# mag-baro.net
KiCad netlist of a schematic drawn in EAGLE
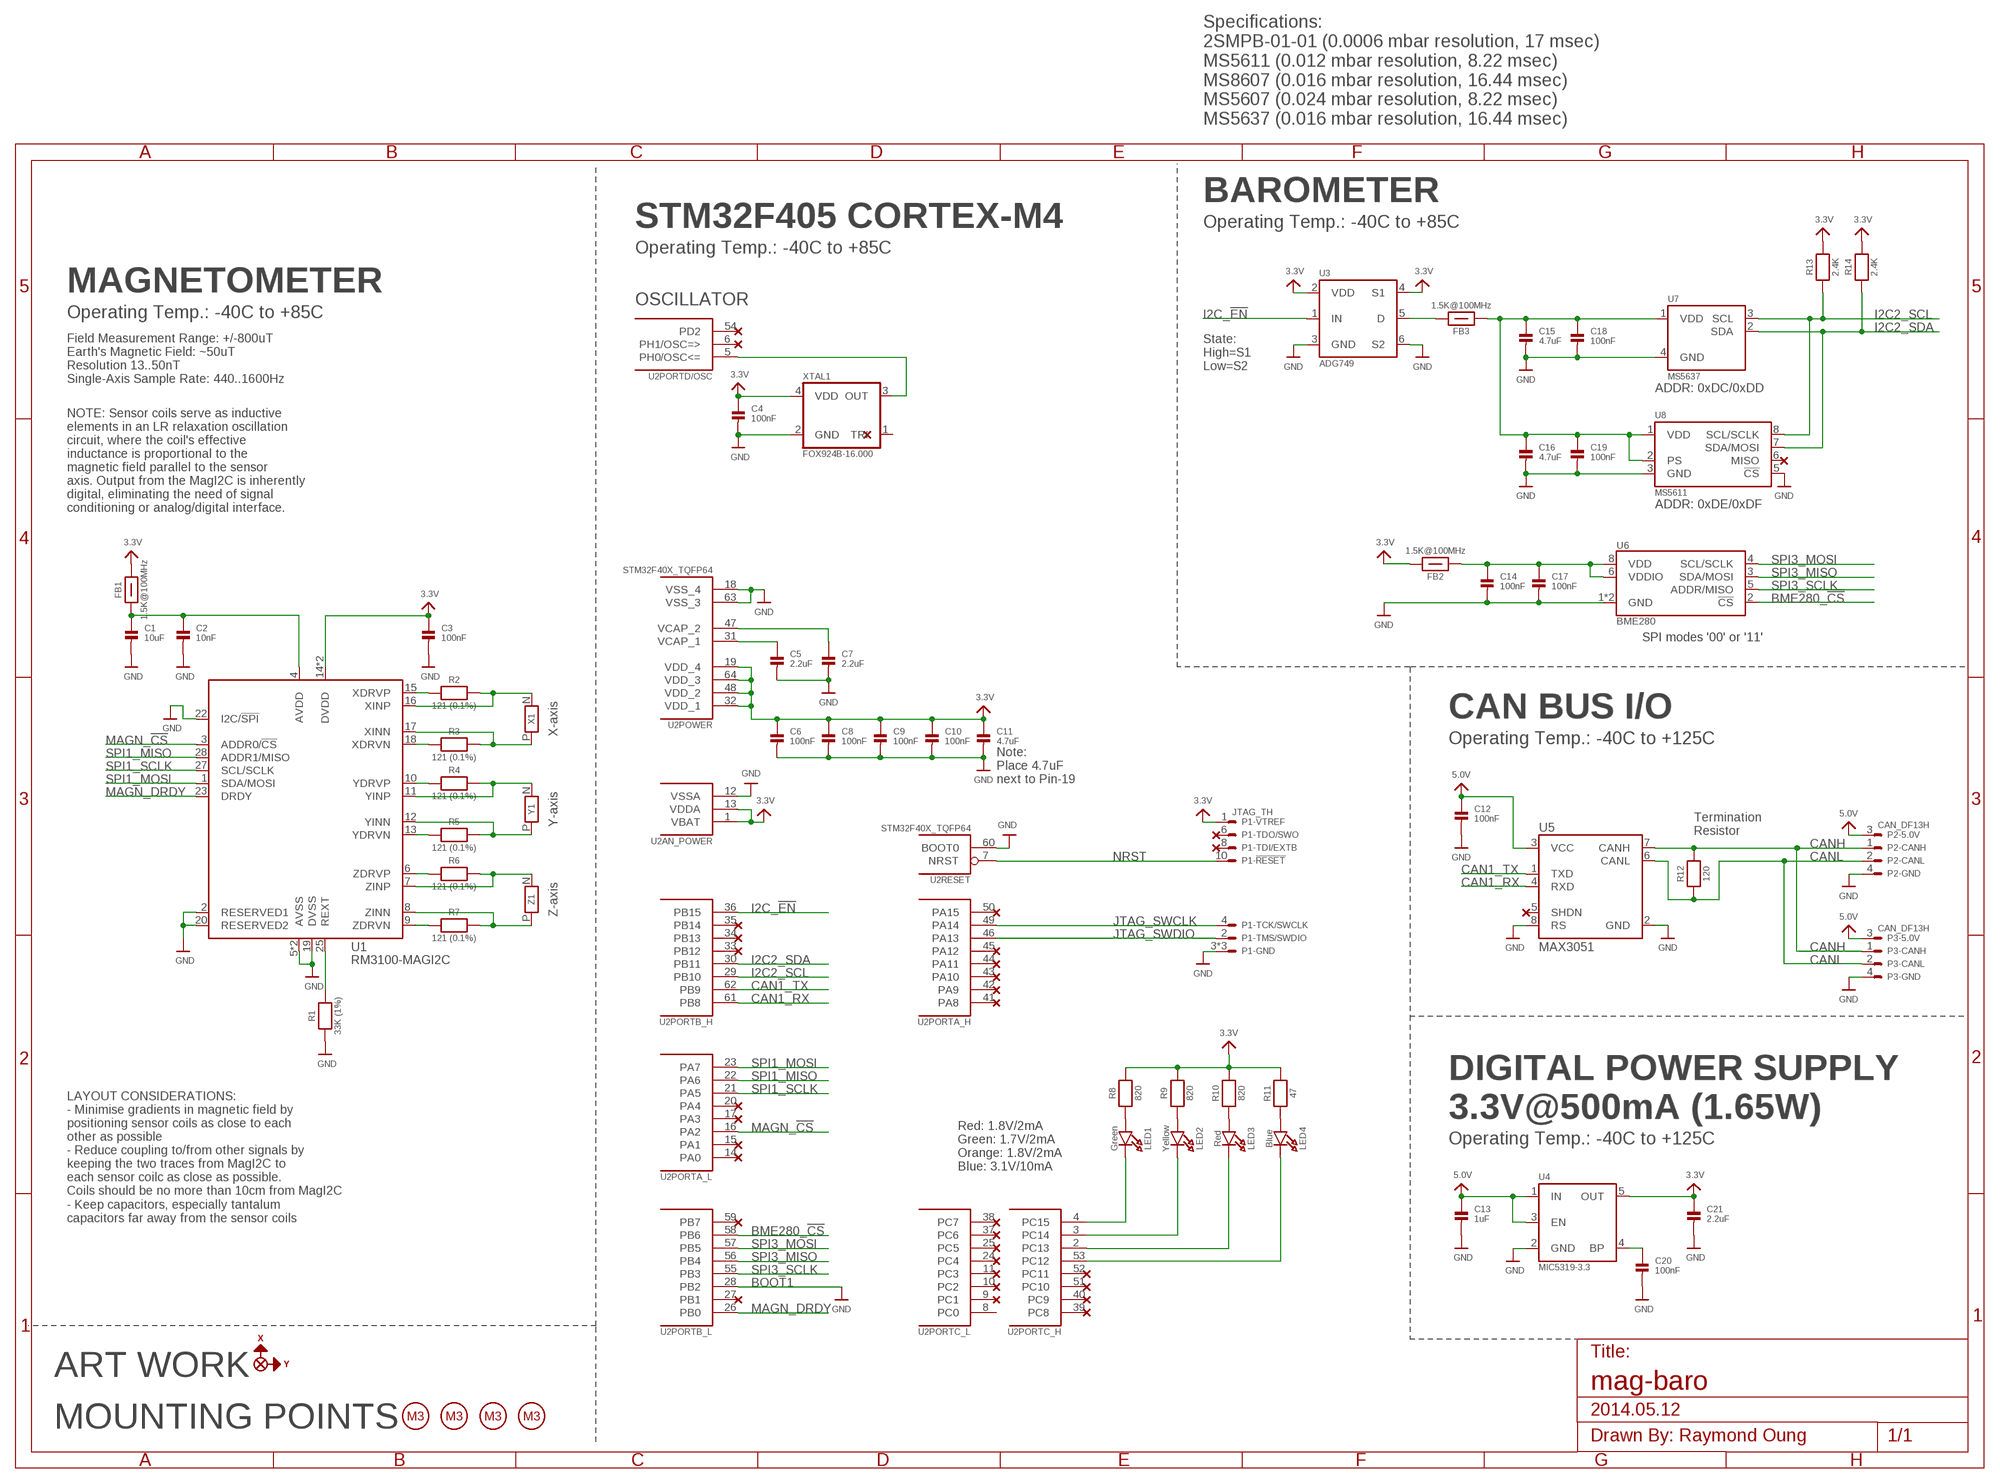
[diagram p0: schematic, sheet 1]

(export (version "E")
  (design (tool "Eeschema 10.0.6"))
  (components
    (comp (ref "AXIS3D2")
      (value "AXIS3D_DOWN")
      (footprint "eagle-import:AXIS3D_DOWN")
      (libsource (lib "eagle-import") (part "AXIS3D_DOWN"))
    )
    (comp (ref "C1")
      (value "10uF")
      (footprint "eagle-import:0402")
      (libsource (lib "eagle-import") (part "CAP_CERAMIC0402"))
    )
    (comp (ref "C2")
      (value "10nF")
      (footprint "eagle-import:0402")
      (libsource (lib "eagle-import") (part "CAP_CERAMIC0402"))
    )
    (comp (ref "C3")
      (value "100nF")
      (footprint "eagle-import:0402")
      (libsource (lib "eagle-import") (part "CAP_CERAMIC0402"))
    )
    (comp (ref "C4")
      (value "100nF")
      (footprint "eagle-import:0402")
      (libsource (lib "eagle-import") (part "CAP_CERAMIC0402"))
    )
    (comp (ref "C5")
      (value "2.2uF")
      (footprint "eagle-import:0402")
      (libsource (lib "eagle-import") (part "CAP_CERAMIC0402"))
    )
    (comp (ref "C6")
      (value "100nF")
      (footprint "eagle-import:0402")
      (libsource (lib "eagle-import") (part "CAP_CERAMIC0402"))
    )
    (comp (ref "C7")
      (value "2.2uF")
      (footprint "eagle-import:0402")
      (libsource (lib "eagle-import") (part "CAP_CERAMIC0402"))
    )
    (comp (ref "C8")
      (value "100nF")
      (footprint "eagle-import:0402")
      (libsource (lib "eagle-import") (part "CAP_CERAMIC0402"))
    )
    (comp (ref "C9")
      (value "100nF")
      (footprint "eagle-import:0402")
      (libsource (lib "eagle-import") (part "CAP_CERAMIC0402"))
    )
    (comp (ref "C10")
      (value "100nF")
      (footprint "eagle-import:0402")
      (libsource (lib "eagle-import") (part "CAP_CERAMIC0402"))
    )
    (comp (ref "C11")
      (value "4.7uF")
      (footprint "eagle-import:0402")
      (libsource (lib "eagle-import") (part "CAP_CERAMIC0402"))
    )
    (comp (ref "C12")
      (value "100nF")
      (footprint "eagle-import:0402")
      (libsource (lib "eagle-import") (part "CAP_CERAMIC0402"))
    )
    (comp (ref "C13")
      (value "1uF")
      (footprint "eagle-import:0402")
      (libsource (lib "eagle-import") (part "CAP_CERAMIC0402"))
    )
    (comp (ref "C14")
      (value "100nF")
      (footprint "eagle-import:0402")
      (libsource (lib "eagle-import") (part "CAP_CERAMIC0402"))
    )
    (comp (ref "C15")
      (value "4.7uF")
      (footprint "eagle-import:0402")
      (libsource (lib "eagle-import") (part "CAP_CERAMIC0402"))
    )
    (comp (ref "C16")
      (value "4.7uF")
      (footprint "eagle-import:0402")
      (libsource (lib "eagle-import") (part "CAP_CERAMIC0402"))
    )
    (comp (ref "C17")
      (value "100nF")
      (footprint "eagle-import:0402")
      (libsource (lib "eagle-import") (part "CAP_CERAMIC0402"))
    )
    (comp (ref "C18")
      (value "100nF")
      (footprint "eagle-import:0402")
      (libsource (lib "eagle-import") (part "CAP_CERAMIC0402"))
    )
    (comp (ref "C19")
      (value "100nF")
      (footprint "eagle-import:0402")
      (libsource (lib "eagle-import") (part "CAP_CERAMIC0402"))
    )
    (comp (ref "C20")
      (value "100nF")
      (footprint "eagle-import:0402")
      (libsource (lib "eagle-import") (part "CAP_CERAMIC0402"))
    )
    (comp (ref "C21")
      (value "2.2uF")
      (footprint "eagle-import:0402")
      (libsource (lib "eagle-import") (part "CAP_CERAMIC0402"))
    )
    (comp (ref "FB1")
      (value "1.5K@100MHz")
      (footprint "eagle-import:0402")
      (libsource (lib "eagle-import") (part "FERRITE_0402"))
    )
    (comp (ref "FB2")
      (value "1.5K@100MHz")
      (footprint "eagle-import:0402")
      (libsource (lib "eagle-import") (part "FERRITE_0402"))
    )
    (comp (ref "FB3")
      (value "1.5K@100MHz")
      (footprint "eagle-import:0402")
      (libsource (lib "eagle-import") (part "FERRITE_0402"))
    )
    (comp (ref "LED1")
      (value "Green")
      (footprint "eagle-import:CHIPLED_0603")
      (libsource (lib "eagle-import") (part "LED_0603"))
    )
    (comp (ref "LED2")
      (value "Yellow")
      (footprint "eagle-import:CHIPLED_0603")
      (libsource (lib "eagle-import") (part "LED_0603"))
    )
    (comp (ref "LED3")
      (value "Red")
      (footprint "eagle-import:CHIPLED_0603")
      (libsource (lib "eagle-import") (part "LED_0603"))
    )
    (comp (ref "LED4")
      (value "Blue")
      (footprint "eagle-import:CHIPLED_0603")
      (libsource (lib "eagle-import") (part "LED_0603"))
    )
    (comp (ref "MP1")
      (value "M3_5")
      (footprint "eagle-import:MP_M3-5")
      (libsource (lib "eagle-import") (part "M3_5"))
    )
    (comp (ref "MP2")
      (value "M3_5")
      (footprint "eagle-import:MP_M3-5")
      (libsource (lib "eagle-import") (part "M3_5"))
    )
    (comp (ref "MP3")
      (value "M3_5")
      (footprint "eagle-import:MP_M3-5")
      (libsource (lib "eagle-import") (part "M3_5"))
    )
    (comp (ref "MP4")
      (value "M3_5")
      (footprint "eagle-import:MP_M3-5")
      (libsource (lib "eagle-import") (part "M3_5"))
    )
    (comp (ref "P1")
      (value "JTAG_TH")
      (footprint "eagle-import:FTSH-105-01-XXX-DV")
      (libsource (lib "eagle-import") (part "JTAG_TH"))
    )
    (comp (ref "P2")
      (value "CAN_DF13H")
      (footprint "eagle-import:DF13A-4P-1.25H")
      (libsource (lib "eagle-import") (part "CAN_DF13H"))
    )
    (comp (ref "P3")
      (value "CAN_DF13H")
      (footprint "eagle-import:DF13A-4P-1.25H")
      (libsource (lib "eagle-import") (part "CAN_DF13H"))
    )
    (comp (ref "R1")
      (value "33K (1%)")
      (footprint "eagle-import:0402")
      (libsource (lib "eagle-import") (part "RESISTOR0402"))
    )
    (comp (ref "R2")
      (value "121 (0.1%)")
      (footprint "eagle-import:0402")
      (libsource (lib "eagle-import") (part "RESISTOR0402"))
    )
    (comp (ref "R3")
      (value "121 (0.1%)")
      (footprint "eagle-import:0402")
      (libsource (lib "eagle-import") (part "RESISTOR0402"))
    )
    (comp (ref "R4")
      (value "121 (0.1%)")
      (footprint "eagle-import:0402")
      (libsource (lib "eagle-import") (part "RESISTOR0402"))
    )
    (comp (ref "R5")
      (value "121 (0.1%)")
      (footprint "eagle-import:0402")
      (libsource (lib "eagle-import") (part "RESISTOR0402"))
    )
    (comp (ref "R6")
      (value "121 (0.1%)")
      (footprint "eagle-import:0402")
      (libsource (lib "eagle-import") (part "RESISTOR0402"))
    )
    (comp (ref "R7")
      (value "121 (0.1%)")
      (footprint "eagle-import:0402")
      (libsource (lib "eagle-import") (part "RESISTOR0402"))
    )
    (comp (ref "R8")
      (value "820")
      (footprint "eagle-import:0402")
      (libsource (lib "eagle-import") (part "RESISTOR0402"))
    )
    (comp (ref "R9")
      (value "820")
      (footprint "eagle-import:0402")
      (libsource (lib "eagle-import") (part "RESISTOR0402"))
    )
    (comp (ref "R10")
      (value "820")
      (footprint "eagle-import:0402")
      (libsource (lib "eagle-import") (part "RESISTOR0402"))
    )
    (comp (ref "R11")
      (value "47")
      (footprint "eagle-import:0402")
      (libsource (lib "eagle-import") (part "RESISTOR0402"))
    )
    (comp (ref "R12")
      (value "120")
      (footprint "eagle-import:0603")
      (libsource (lib "eagle-import") (part "RESISTOR0603"))
    )
    (comp (ref "R13")
      (value "2.4K")
      (footprint "eagle-import:0402")
      (libsource (lib "eagle-import") (part "RESISTOR0402"))
    )
    (comp (ref "R14")
      (value "2.4K")
      (footprint "eagle-import:0402")
      (libsource (lib "eagle-import") (part "RESISTOR0402"))
    )
    (comp (ref "U1")
      (value "RM3100-MAGI2C")
      (footprint "eagle-import:RM3100-MAGI2C")
      (libsource (lib "eagle-import") (part "RM3100-MAGI2C"))
    )
    (comp (ref "U2")
      (value "STM32F40X_TQFP64")
      (footprint "eagle-import:TQFP64")
      (libsource (lib "eagle-import") (part "STM32F40X_TQFP64"))
    )
    (comp (ref "U3")
      (value "ADG749")
      (footprint "eagle-import:SOT363")
      (libsource (lib "eagle-import") (part "ADG749"))
    )
    (comp (ref "U4")
      (value "MIC5319-3.3")
      (footprint "eagle-import:SOT23-5")
      (libsource (lib "eagle-import") (part "MIC5319-3.3"))
    )
    (comp (ref "U5")
      (value "MAX3051")
      (footprint "eagle-import:SOT23-8")
      (libsource (lib "eagle-import") (part "MAX3051"))
    )
    (comp (ref "U6")
      (value "BME280")
      (footprint "eagle-import:BME280_LGA_MANUAL")
      (libsource (lib "eagle-import") (part "BME280_MANUAL"))
    )
    (comp (ref "U7")
      (value "MS5637")
      (footprint "eagle-import:MS5637")
      (libsource (lib "eagle-import") (part "MS5637"))
    )
    (comp (ref "U8")
      (value "MS5611")
      (footprint "eagle-import:MS5611")
      (libsource (lib "eagle-import") (part "MS5611"))
    )
    (comp (ref "X1")
      (value "RM3XXX-SEN-X")
      (footprint "eagle-import:RM3XXX-SEN-XY")
      (libsource (lib "eagle-import") (part "RM3XXX-SEN-X"))
    )
    (comp (ref "XTAL1")
      (value "FOX924B-16.000")
      (footprint "eagle-import:OSCILLATOR-5.0X3.2A")
      (libsource (lib "eagle-import") (part "TCXO_5.0X3.2A"))
    )
    (comp (ref "Y1")
      (value "RM3XXX-SEN-Y")
      (footprint "eagle-import:RM3XXX-SEN-XY")
      (libsource (lib "eagle-import") (part "RM3XXX-SEN-Y"))
    )
    (comp (ref "Z1")
      (value "RM3XXX-SEN-Z")
      (footprint "eagle-import:RM3XXX-SEN_Z")
      (libsource (lib "eagle-import") (part "RM3XXX-SEN-Z"))
    )
  )
  (nets
    (net (code "1") (name "/BME280_~{CS}") (class "Default")
      (node (ref "U2") (pin "58") (pinfunction "PB6_58") (pintype "bidirectional"))
      (node (ref "U6") (pin "2") (pinfunction "~{CS}_2") (pintype "bidirectional"))
    )
    (net (code "2") (name "/CAN1_RX") (class "Default")
      (node (ref "U2") (pin "61") (pinfunction "PB8_61") (pintype "bidirectional"))
      (node (ref "U5") (pin "4") (pinfunction "RXD_4") (pintype "bidirectional"))
    )
    (net (code "3") (name "/CAN1_TX") (class "Default")
      (node (ref "U2") (pin "62") (pinfunction "PB9_62") (pintype "bidirectional"))
      (node (ref "U5") (pin "1") (pinfunction "TXD_1") (pintype "bidirectional"))
    )
    (net (code "4") (name "/CANH") (class "Default")
      (node (ref "P2") (pin "1") (pinfunction "S_1") (pintype "passive"))
      (node (ref "P3") (pin "1") (pinfunction "S_1") (pintype "passive"))
      (node (ref "R12") (pin "2") (pinfunction "2_2") (pintype "passive"))
      (node (ref "U5") (pin "7") (pinfunction "CANH_7") (pintype "bidirectional"))
    )
    (net (code "5") (name "/CANL") (class "Default")
      (node (ref "P2") (pin "2") (pinfunction "S_2") (pintype "passive"))
      (node (ref "P3") (pin "2") (pinfunction "S_2") (pintype "passive"))
      (node (ref "R12") (pin "1") (pinfunction "1_1") (pintype "passive"))
      (node (ref "U5") (pin "6") (pinfunction "CANL_6") (pintype "bidirectional"))
    )
    (net (code "6") (name "/I2C2_SCL") (class "Default")
      (node (ref "R13") (pin "1") (pinfunction "1_1") (pintype "passive"))
      (node (ref "U2") (pin "29") (pinfunction "PB10_29") (pintype "bidirectional"))
      (node (ref "U7") (pin "3") (pinfunction "SCL_3") (pintype "bidirectional"))
      (node (ref "U8") (pin "8") (pinfunction "SCL/SCLK_8") (pintype "bidirectional"))
    )
    (net (code "7") (name "/I2C2_SDA") (class "Default")
      (node (ref "R14") (pin "1") (pinfunction "1_1") (pintype "passive"))
      (node (ref "U2") (pin "30") (pinfunction "PB11_30") (pintype "bidirectional"))
      (node (ref "U7") (pin "2") (pinfunction "SDA_2") (pintype "bidirectional"))
      (node (ref "U8") (pin "7") (pinfunction "SDA/MOSI_7") (pintype "bidirectional"))
    )
    (net (code "8") (name "/I2C_~{EN}") (class "Default")
      (node (ref "U2") (pin "36") (pinfunction "PB15_36") (pintype "bidirectional"))
      (node (ref "U3") (pin "1") (pinfunction "IN_1") (pintype "bidirectional"))
    )
    (net (code "9") (name "/JTAG_SWCLK") (class "Default")
      (node (ref "P1") (pin "4") (pinfunction "S_4") (pintype "passive"))
      (node (ref "U2") (pin "49") (pinfunction "PA14_49") (pintype "bidirectional"))
    )
    (net (code "10") (name "/JTAG_SWDIO") (class "Default")
      (node (ref "P1") (pin "2") (pinfunction "S_2") (pintype "passive"))
      (node (ref "U2") (pin "46") (pinfunction "PA13_46") (pintype "bidirectional"))
    )
    (net (code "11") (name "/MAGN_DRDY") (class "Default")
      (node (ref "U1") (pin "23") (pinfunction "DRDY_23") (pintype "bidirectional"))
      (node (ref "U2") (pin "26") (pinfunction "PB0_26") (pintype "bidirectional"))
    )
    (net (code "12") (name "/MAGN_~{CS}") (class "Default")
      (node (ref "U1") (pin "3") (pinfunction "ADDR0/~{CS}_3") (pintype "bidirectional"))
      (node (ref "U2") (pin "16") (pinfunction "PA2_16") (pintype "bidirectional"))
    )
    (net (code "13") (name "/NRST") (class "Default")
      (node (ref "P1") (pin "10") (pinfunction "S_10") (pintype "passive"))
      (node (ref "U2") (pin "7") (pinfunction "NRST_7") (pintype "input"))
    )
    (net (code "14") (name "/SPI1_MISO") (class "Default")
      (node (ref "U1") (pin "28") (pinfunction "ADDR1/MISO_28") (pintype "bidirectional"))
      (node (ref "U2") (pin "22") (pinfunction "PA6_22") (pintype "bidirectional"))
    )
    (net (code "15") (name "/SPI1_MOSI") (class "Default")
      (node (ref "U1") (pin "1") (pinfunction "SDA/MOSI_1") (pintype "bidirectional"))
      (node (ref "U2") (pin "23") (pinfunction "PA7_23") (pintype "bidirectional"))
    )
    (net (code "16") (name "/SPI1_SCLK") (class "Default")
      (node (ref "U1") (pin "27") (pinfunction "SCL/SCLK_27") (pintype "bidirectional"))
      (node (ref "U2") (pin "21") (pinfunction "PA5_21") (pintype "bidirectional"))
    )
    (net (code "17") (name "/SPI3_MISO") (class "Default")
      (node (ref "U2") (pin "56") (pinfunction "PB4_56") (pintype "bidirectional"))
      (node (ref "U6") (pin "5") (pinfunction "ADDR/MISO_5") (pintype "bidirectional"))
    )
    (net (code "18") (name "/SPI3_MOSI") (class "Default")
      (node (ref "U2") (pin "57") (pinfunction "PB5_57") (pintype "bidirectional"))
      (node (ref "U6") (pin "3") (pinfunction "SDA/MOSI_3") (pintype "bidirectional"))
    )
    (net (code "19") (name "/SPI3_SCLK") (class "Default")
      (node (ref "U2") (pin "55") (pinfunction "PB3_55") (pintype "bidirectional"))
      (node (ref "U6") (pin "4") (pinfunction "SCL/SCLK_4") (pintype "bidirectional"))
    )
    (net (code "20") (name "3.3V") (class "Default")
      (node (ref "C10") (pin "1") (pinfunction "P$1_1") (pintype "passive"))
      (node (ref "C11") (pin "1") (pinfunction "P$1_1") (pintype "passive"))
      (node (ref "C21") (pin "1") (pinfunction "P$1_1") (pintype "passive"))
      (node (ref "C3") (pin "1") (pinfunction "P$1_1") (pintype "passive"))
      (node (ref "C4") (pin "1") (pinfunction "P$1_1") (pintype "passive"))
      (node (ref "C6") (pin "1") (pinfunction "P$1_1") (pintype "passive"))
      (node (ref "C8") (pin "1") (pinfunction "P$1_1") (pintype "passive"))
      (node (ref "C9") (pin "1") (pinfunction "P$1_1") (pintype "passive"))
      (node (ref "FB1") (pin "2") (pinfunction "2_2") (pintype "passive"))
      (node (ref "FB2") (pin "2") (pinfunction "2_2") (pintype "passive"))
      (node (ref "P1") (pin "1") (pinfunction "S_1") (pintype "passive"))
      (node (ref "R10") (pin "2") (pinfunction "2_2") (pintype "passive"))
      (node (ref "R11") (pin "2") (pinfunction "2_2") (pintype "passive"))
      (node (ref "R13") (pin "2") (pinfunction "2_2") (pintype "passive"))
      (node (ref "R14") (pin "2") (pinfunction "2_2") (pintype "passive"))
      (node (ref "R8") (pin "2") (pinfunction "2_2") (pintype "passive"))
      (node (ref "R9") (pin "2") (pinfunction "2_2") (pintype "passive"))
      (node (ref "U1") (pin "14") (pinfunction "DVDD_14") (pintype "bidirectional"))
      (node (ref "U1") (pin "26") (pinfunction "DVDD_26") (pintype "bidirectional"))
      (node (ref "U2") (pin "1") (pinfunction "VBAT_1") (pintype "power_in"))
      (node (ref "U2") (pin "13") (pinfunction "VDDA_13") (pintype "power_in"))
      (node (ref "U2") (pin "19") (pinfunction "VDD_4_19") (pintype "power_in"))
      (node (ref "U2") (pin "32") (pinfunction "VDD_1_32") (pintype "power_in"))
      (node (ref "U2") (pin "48") (pinfunction "VDD_2_48") (pintype "power_in"))
      (node (ref "U2") (pin "64") (pinfunction "VDD_3_64") (pintype "power_in"))
      (node (ref "U3") (pin "2") (pinfunction "VDD_2") (pintype "bidirectional"))
      (node (ref "U3") (pin "4") (pinfunction "S1_4") (pintype "bidirectional"))
      (node (ref "U4") (pin "5") (pinfunction "OUT_5") (pintype "bidirectional"))
      (node (ref "XTAL1") (pin "4") (pinfunction "VDD_4") (pintype "bidirectional"))
    )
    (net (code "21") (name "5.0V") (class "Default")
      (node (ref "C12") (pin "1") (pinfunction "P$1_1") (pintype "passive"))
      (node (ref "C13") (pin "1") (pinfunction "P$1_1") (pintype "passive"))
      (node (ref "P2") (pin "3") (pinfunction "S_3") (pintype "passive"))
      (node (ref "P3") (pin "3") (pinfunction "S_3") (pintype "passive"))
      (node (ref "U4") (pin "1") (pinfunction "IN_1") (pintype "bidirectional"))
      (node (ref "U4") (pin "3") (pinfunction "EN_3") (pintype "bidirectional"))
      (node (ref "U5") (pin "3") (pinfunction "VCC_3") (pintype "bidirectional"))
    )
    (net (code "22") (name "GND") (class "Default")
      (node (ref "C1") (pin "2") (pinfunction "P$2_2") (pintype "passive"))
      (node (ref "C10") (pin "2") (pinfunction "P$2_2") (pintype "passive"))
      (node (ref "C11") (pin "2") (pinfunction "P$2_2") (pintype "passive"))
      (node (ref "C12") (pin "2") (pinfunction "P$2_2") (pintype "passive"))
      (node (ref "C13") (pin "2") (pinfunction "P$2_2") (pintype "passive"))
      (node (ref "C14") (pin "2") (pinfunction "P$2_2") (pintype "passive"))
      (node (ref "C15") (pin "2") (pinfunction "P$2_2") (pintype "passive"))
      (node (ref "C16") (pin "2") (pinfunction "P$2_2") (pintype "passive"))
      (node (ref "C17") (pin "2") (pinfunction "P$2_2") (pintype "passive"))
      (node (ref "C18") (pin "2") (pinfunction "P$2_2") (pintype "passive"))
      (node (ref "C19") (pin "2") (pinfunction "P$2_2") (pintype "passive"))
      (node (ref "C2") (pin "2") (pinfunction "P$2_2") (pintype "passive"))
      (node (ref "C20") (pin "2") (pinfunction "P$2_2") (pintype "passive"))
      (node (ref "C21") (pin "2") (pinfunction "P$2_2") (pintype "passive"))
      (node (ref "C3") (pin "2") (pinfunction "P$2_2") (pintype "passive"))
      (node (ref "C4") (pin "2") (pinfunction "P$2_2") (pintype "passive"))
      (node (ref "C5") (pin "2") (pinfunction "P$2_2") (pintype "passive"))
      (node (ref "C6") (pin "2") (pinfunction "P$2_2") (pintype "passive"))
      (node (ref "C7") (pin "2") (pinfunction "P$2_2") (pintype "passive"))
      (node (ref "C8") (pin "2") (pinfunction "P$2_2") (pintype "passive"))
      (node (ref "C9") (pin "2") (pinfunction "P$2_2") (pintype "passive"))
      (node (ref "P1") (pin "3") (pinfunction "S_3") (pintype "passive"))
      (node (ref "P1") (pin "5") (pinfunction "S_5") (pintype "passive"))
      (node (ref "P1") (pin "9") (pinfunction "S_9") (pintype "passive"))
      (node (ref "P2") (pin "4") (pinfunction "S_4") (pintype "passive"))
      (node (ref "P3") (pin "4") (pinfunction "S_4") (pintype "passive"))
      (node (ref "R1") (pin "1") (pinfunction "1_1") (pintype "passive"))
      (node (ref "U1") (pin "19") (pinfunction "DVSS_19") (pintype "bidirectional"))
      (node (ref "U1") (pin "2") (pinfunction "RESERVED1_2") (pintype "bidirectional"))
      (node (ref "U1") (pin "20") (pinfunction "RESERVED2_20") (pintype "bidirectional"))
      (node (ref "U1") (pin "22") (pinfunction "I2C/~{SPI}_22") (pintype "bidirectional"))
      (node (ref "U1") (pin "5") (pinfunction "AVSS_5") (pintype "bidirectional"))
      (node (ref "U1") (pin "PAD") (pinfunction "AVSS_PAD") (pintype "bidirectional"))
      (node (ref "U2") (pin "12") (pinfunction "VSSA_12") (pintype "power_in"))
      (node (ref "U2") (pin "18") (pinfunction "VSS_4_18") (pintype "power_in"))
      (node (ref "U2") (pin "28") (pinfunction "PB2_28") (pintype "bidirectional"))
      (node (ref "U2") (pin "60") (pinfunction "BOOT0_60") (pintype "input"))
      (node (ref "U2") (pin "63") (pinfunction "VSS_3_63") (pintype "power_in"))
      (node (ref "U3") (pin "3") (pinfunction "GND_3") (pintype "bidirectional"))
      (node (ref "U3") (pin "6") (pinfunction "S2_6") (pintype "bidirectional"))
      (node (ref "U4") (pin "2") (pinfunction "GND_2") (pintype "bidirectional"))
      (node (ref "U5") (pin "2") (pinfunction "GND_2") (pintype "bidirectional"))
      (node (ref "U5") (pin "8") (pinfunction "RS_8") (pintype "bidirectional"))
      (node (ref "U6") (pin "1") (pinfunction "GND_1") (pintype "power_in"))
      (node (ref "U6") (pin "7") (pinfunction "GND_7") (pintype "power_in"))
      (node (ref "U7") (pin "4") (pinfunction "GND_4") (pintype "power_in"))
      (node (ref "U8") (pin "3") (pinfunction "GND_3") (pintype "power_in"))
      (node (ref "U8") (pin "5") (pinfunction "~{CS}_5") (pintype "bidirectional"))
      (node (ref "XTAL1") (pin "2") (pinfunction "GND_2") (pintype "bidirectional"))
    )
    (net (code "23") (name "Net-(C1-P$1)") (class "Default")
      (node (ref "C1") (pin "1") (pinfunction "P$1_1") (pintype "passive"))
      (node (ref "C2") (pin "1") (pinfunction "P$1_1") (pintype "passive"))
      (node (ref "FB1") (pin "1") (pinfunction "1_1") (pintype "passive"))
      (node (ref "U1") (pin "4") (pinfunction "AVDD_4") (pintype "bidirectional"))
    )
    (net (code "24") (name "Net-(C5-P$1)") (class "Default")
      (node (ref "C5") (pin "1") (pinfunction "P$1_1") (pintype "passive"))
      (node (ref "U2") (pin "31") (pinfunction "VCAP_1_31") (pintype "power_in"))
    )
    (net (code "25") (name "Net-(C7-P$1)") (class "Default")
      (node (ref "C7") (pin "1") (pinfunction "P$1_1") (pintype "passive"))
      (node (ref "U2") (pin "47") (pinfunction "VCAP_2_47") (pintype "power_in"))
    )
    (net (code "26") (name "Net-(C14-P$1)") (class "Default")
      (node (ref "C14") (pin "1") (pinfunction "P$1_1") (pintype "passive"))
      (node (ref "C17") (pin "1") (pinfunction "P$1_1") (pintype "passive"))
      (node (ref "FB2") (pin "1") (pinfunction "1_1") (pintype "passive"))
      (node (ref "U6") (pin "6") (pinfunction "VDDIO_6") (pintype "power_in"))
      (node (ref "U6") (pin "8") (pinfunction "VDD_8") (pintype "power_in"))
    )
    (net (code "27") (name "Net-(C15-P$1)") (class "Default")
      (node (ref "C15") (pin "1") (pinfunction "P$1_1") (pintype "passive"))
      (node (ref "C16") (pin "1") (pinfunction "P$1_1") (pintype "passive"))
      (node (ref "C18") (pin "1") (pinfunction "P$1_1") (pintype "passive"))
      (node (ref "C19") (pin "1") (pinfunction "P$1_1") (pintype "passive"))
      (node (ref "FB3") (pin "1") (pinfunction "1_1") (pintype "passive"))
      (node (ref "U7") (pin "1") (pinfunction "VDD_1") (pintype "power_in"))
      (node (ref "U8") (pin "1") (pinfunction "VDD_1") (pintype "power_in"))
      (node (ref "U8") (pin "2") (pinfunction "PS_2") (pintype "passive"))
    )
    (net (code "28") (name "Net-(C20-P$1)") (class "Default")
      (node (ref "C20") (pin "1") (pinfunction "P$1_1") (pintype "passive"))
      (node (ref "U4") (pin "4") (pinfunction "BP_4") (pintype "bidirectional"))
    )
    (net (code "29") (name "Net-(LED1-PadA)") (class "Default")
      (node (ref "LED1") (pin "A") (pinfunction "A_A") (pintype "passive"))
      (node (ref "R8") (pin "1") (pinfunction "1_1") (pintype "passive"))
    )
    (net (code "30") (name "Net-(LED2-PadA)") (class "Default")
      (node (ref "LED2") (pin "A") (pinfunction "A_A") (pintype "passive"))
      (node (ref "R9") (pin "1") (pinfunction "1_1") (pintype "passive"))
    )
    (net (code "31") (name "Net-(LED3-PadA)") (class "Default")
      (node (ref "LED3") (pin "A") (pinfunction "A_A") (pintype "passive"))
      (node (ref "R10") (pin "1") (pinfunction "1_1") (pintype "passive"))
    )
    (net (code "32") (name "Net-(LED4-PadA)") (class "Default")
      (node (ref "LED4") (pin "A") (pinfunction "A_A") (pintype "passive"))
      (node (ref "R11") (pin "1") (pinfunction "1_1") (pintype "passive"))
    )
    (net (code "33") (name "Net-(U1-REXT)") (class "Default")
      (node (ref "R1") (pin "2") (pinfunction "2_2") (pintype "passive"))
      (node (ref "U1") (pin "25") (pinfunction "REXT_25") (pintype "bidirectional"))
    )
    (net (code "34") (name "Net-(U1-XDRVN)") (class "Default")
      (node (ref "R3") (pin "1") (pinfunction "1_1") (pintype "passive"))
      (node (ref "U1") (pin "18") (pinfunction "XDRVN_18") (pintype "bidirectional"))
    )
    (net (code "35") (name "Net-(U1-XDRVP)") (class "Default")
      (node (ref "R2") (pin "1") (pinfunction "1_1") (pintype "passive"))
      (node (ref "U1") (pin "15") (pinfunction "XDRVP_15") (pintype "bidirectional"))
    )
    (net (code "36") (name "Net-(U1-XINN)") (class "Default")
      (node (ref "R3") (pin "2") (pinfunction "2_2") (pintype "passive"))
      (node (ref "U1") (pin "17") (pinfunction "XINN_17") (pintype "bidirectional"))
      (node (ref "X1") (pin "P") (pinfunction "P_P") (pintype "bidirectional"))
    )
    (net (code "37") (name "Net-(U1-XINP)") (class "Default")
      (node (ref "R2") (pin "2") (pinfunction "2_2") (pintype "passive"))
      (node (ref "U1") (pin "16") (pinfunction "XINP_16") (pintype "bidirectional"))
      (node (ref "X1") (pin "N") (pinfunction "N_N") (pintype "bidirectional"))
    )
    (net (code "38") (name "Net-(U1-YDRVN)") (class "Default")
      (node (ref "R5") (pin "1") (pinfunction "1_1") (pintype "passive"))
      (node (ref "U1") (pin "13") (pinfunction "YDRVN_13") (pintype "bidirectional"))
    )
    (net (code "39") (name "Net-(U1-YDRVP)") (class "Default")
      (node (ref "R4") (pin "1") (pinfunction "1_1") (pintype "passive"))
      (node (ref "U1") (pin "10") (pinfunction "YDRVP_10") (pintype "bidirectional"))
    )
    (net (code "40") (name "Net-(U1-YINN)") (class "Default")
      (node (ref "R5") (pin "2") (pinfunction "2_2") (pintype "passive"))
      (node (ref "U1") (pin "12") (pinfunction "YINN_12") (pintype "bidirectional"))
      (node (ref "Y1") (pin "P") (pinfunction "P_P") (pintype "bidirectional"))
    )
    (net (code "41") (name "Net-(U1-YINP)") (class "Default")
      (node (ref "R4") (pin "2") (pinfunction "2_2") (pintype "passive"))
      (node (ref "U1") (pin "11") (pinfunction "YINP_11") (pintype "bidirectional"))
      (node (ref "Y1") (pin "N") (pinfunction "N_N") (pintype "bidirectional"))
    )
    (net (code "42") (name "Net-(U1-ZDRVN)") (class "Default")
      (node (ref "R7") (pin "1") (pinfunction "1_1") (pintype "passive"))
      (node (ref "U1") (pin "9") (pinfunction "ZDRVN_9") (pintype "bidirectional"))
    )
    (net (code "43") (name "Net-(U1-ZDRVP)") (class "Default")
      (node (ref "R6") (pin "1") (pinfunction "1_1") (pintype "passive"))
      (node (ref "U1") (pin "6") (pinfunction "ZDRVP_6") (pintype "bidirectional"))
    )
    (net (code "44") (name "Net-(U1-ZINN)") (class "Default")
      (node (ref "R7") (pin "2") (pinfunction "2_2") (pintype "passive"))
      (node (ref "U1") (pin "8") (pinfunction "ZINN_8") (pintype "bidirectional"))
      (node (ref "Z1") (pin "P") (pinfunction "P_P") (pintype "bidirectional"))
    )
    (net (code "45") (name "Net-(U1-ZINP)") (class "Default")
      (node (ref "R6") (pin "2") (pinfunction "2_2") (pintype "passive"))
      (node (ref "U1") (pin "7") (pinfunction "ZINP_7") (pintype "bidirectional"))
      (node (ref "Z1") (pin "N") (pinfunction "N_N") (pintype "bidirectional"))
    )
    (net (code "46") (name "Net-(U2F-PC12)") (class "Default")
      (node (ref "LED4") (pin "C") (pinfunction "C_C") (pintype "passive"))
      (node (ref "U2") (pin "53") (pinfunction "PC12_53") (pintype "bidirectional"))
    )
    (net (code "47") (name "Net-(U2F-PC13)") (class "Default")
      (node (ref "LED3") (pin "C") (pinfunction "C_C") (pintype "passive"))
      (node (ref "U2") (pin "2") (pinfunction "PC13_2") (pintype "bidirectional"))
    )
    (net (code "48") (name "Net-(U2F-PC14)") (class "Default")
      (node (ref "LED2") (pin "C") (pinfunction "C_C") (pintype "passive"))
      (node (ref "U2") (pin "3") (pinfunction "PC14_3") (pintype "bidirectional"))
    )
    (net (code "49") (name "Net-(U2F-PC15)") (class "Default")
      (node (ref "LED1") (pin "C") (pinfunction "C_C") (pintype "passive"))
      (node (ref "U2") (pin "4") (pinfunction "PC15_4") (pintype "bidirectional"))
    )
    (net (code "50") (name "Net-(U2H-PH0{slash}OSC<=)") (class "Default")
      (node (ref "U2") (pin "5") (pinfunction "PH0/OSC<=_5") (pintype "bidirectional"))
      (node (ref "XTAL1") (pin "3") (pinfunction "OUT_3") (pintype "bidirectional"))
    )
    (net (code "51") (name "Net-(U3-D)") (class "Default")
      (node (ref "FB3") (pin "2") (pinfunction "2_2") (pintype "passive"))
      (node (ref "U3") (pin "5") (pinfunction "D_5") (pintype "bidirectional"))
    )
    (net (code "52") (name "unconnected-(P1D-S-Pad8)") (class "Default")
      (node (ref "P1") (pin "8") (pinfunction "S_8") (pintype "passive"))
    )
    (net (code "53") (name "unconnected-(P1E-S-Pad6)") (class "Default")
      (node (ref "P1") (pin "6") (pinfunction "S_6") (pintype "passive"))
    )
    (net (code "54") (name "unconnected-(U2B-PA8-Pad41)") (class "Default")
      (node (ref "U2") (pin "41") (pinfunction "PA8_41") (pintype "bidirectional"))
    )
    (net (code "55") (name "unconnected-(U2B-PA9-Pad42)") (class "Default")
      (node (ref "U2") (pin "42") (pinfunction "PA9_42") (pintype "bidirectional"))
    )
    (net (code "56") (name "unconnected-(U2B-PA10-Pad43)") (class "Default")
      (node (ref "U2") (pin "43") (pinfunction "PA10_43") (pintype "bidirectional"))
    )
    (net (code "57") (name "unconnected-(U2B-PA11-Pad44)") (class "Default")
      (node (ref "U2") (pin "44") (pinfunction "PA11_44") (pintype "bidirectional"))
    )
    (net (code "58") (name "unconnected-(U2B-PA12-Pad45)") (class "Default")
      (node (ref "U2") (pin "45") (pinfunction "PA12_45") (pintype "bidirectional"))
    )
    (net (code "59") (name "unconnected-(U2B-PA15-Pad50)") (class "Default")
      (node (ref "U2") (pin "50") (pinfunction "PA15_50") (pintype "bidirectional"))
    )
    (net (code "60") (name "unconnected-(U2C-PA0-Pad14)") (class "Default")
      (node (ref "U2") (pin "14") (pinfunction "PA0_14") (pintype "bidirectional"))
    )
    (net (code "61") (name "unconnected-(U2C-PA1-Pad15)") (class "Default")
      (node (ref "U2") (pin "15") (pinfunction "PA1_15") (pintype "bidirectional"))
    )
    (net (code "62") (name "unconnected-(U2C-PA3-Pad17)") (class "Default")
      (node (ref "U2") (pin "17") (pinfunction "PA3_17") (pintype "bidirectional"))
    )
    (net (code "63") (name "unconnected-(U2C-PA4-Pad20)") (class "Default")
      (node (ref "U2") (pin "20") (pinfunction "PA4_20") (pintype "bidirectional"))
    )
    (net (code "64") (name "unconnected-(U2D-PB12-Pad33)") (class "Default")
      (node (ref "U2") (pin "33") (pinfunction "PB12_33") (pintype "bidirectional"))
    )
    (net (code "65") (name "unconnected-(U2D-PB13-Pad34)") (class "Default")
      (node (ref "U2") (pin "34") (pinfunction "PB13_34") (pintype "bidirectional"))
    )
    (net (code "66") (name "unconnected-(U2D-PB14-Pad35)") (class "Default")
      (node (ref "U2") (pin "35") (pinfunction "PB14_35") (pintype "bidirectional"))
    )
    (net (code "67") (name "unconnected-(U2E-PB1-Pad27)") (class "Default")
      (node (ref "U2") (pin "27") (pinfunction "PB1_27") (pintype "bidirectional"))
    )
    (net (code "68") (name "unconnected-(U2E-PB7-Pad59)") (class "Default")
      (node (ref "U2") (pin "59") (pinfunction "PB7_59") (pintype "bidirectional"))
    )
    (net (code "69") (name "unconnected-(U2F-PC8-Pad39)") (class "Default")
      (node (ref "U2") (pin "39") (pinfunction "PC8_39") (pintype "bidirectional"))
    )
    (net (code "70") (name "unconnected-(U2F-PC9-Pad40)") (class "Default")
      (node (ref "U2") (pin "40") (pinfunction "PC9_40") (pintype "bidirectional"))
    )
    (net (code "71") (name "unconnected-(U2F-PC10-Pad51)") (class "Default")
      (node (ref "U2") (pin "51") (pinfunction "PC10_51") (pintype "bidirectional"))
    )
    (net (code "72") (name "unconnected-(U2F-PC11-Pad52)") (class "Default")
      (node (ref "U2") (pin "52") (pinfunction "PC11_52") (pintype "bidirectional"))
    )
    (net (code "73") (name "unconnected-(U2G-PC0-Pad8)") (class "Default")
      (node (ref "U2") (pin "8") (pinfunction "PC0_8") (pintype "bidirectional"))
    )
    (net (code "74") (name "unconnected-(U2G-PC1-Pad9)") (class "Default")
      (node (ref "U2") (pin "9") (pinfunction "PC1_9") (pintype "bidirectional"))
    )
    (net (code "75") (name "unconnected-(U2G-PC2-Pad10)") (class "Default")
      (node (ref "U2") (pin "10") (pinfunction "PC2_10") (pintype "bidirectional"))
    )
    (net (code "76") (name "unconnected-(U2G-PC3-Pad11)") (class "Default")
      (node (ref "U2") (pin "11") (pinfunction "PC3_11") (pintype "bidirectional"))
    )
    (net (code "77") (name "unconnected-(U2G-PC4-Pad24)") (class "Default")
      (node (ref "U2") (pin "24") (pinfunction "PC4_24") (pintype "bidirectional"))
    )
    (net (code "78") (name "unconnected-(U2G-PC5-Pad25)") (class "Default")
      (node (ref "U2") (pin "25") (pinfunction "PC5_25") (pintype "bidirectional"))
    )
    (net (code "79") (name "unconnected-(U2G-PC6-Pad37)") (class "Default")
      (node (ref "U2") (pin "37") (pinfunction "PC6_37") (pintype "bidirectional"))
    )
    (net (code "80") (name "unconnected-(U2G-PC7-Pad38)") (class "Default")
      (node (ref "U2") (pin "38") (pinfunction "PC7_38") (pintype "bidirectional"))
    )
    (net (code "81") (name "unconnected-(U2H-PD2-Pad54)") (class "Default")
      (node (ref "U2") (pin "54") (pinfunction "PD2_54") (pintype "bidirectional"))
    )
    (net (code "82") (name "unconnected-(U2H-PH1{slash}OSC=>-Pad6)") (class "Default")
      (node (ref "U2") (pin "6") (pinfunction "PH1/OSC=>_6") (pintype "bidirectional"))
    )
    (net (code "83") (name "unconnected-(U5-SHDN-Pad5)") (class "Default")
      (node (ref "U5") (pin "5") (pinfunction "SHDN_5") (pintype "bidirectional"))
    )
    (net (code "84") (name "unconnected-(U8-MISO-Pad6)") (class "Default")
      (node (ref "U8") (pin "6") (pinfunction "MISO_6") (pintype "bidirectional"))
    )
    (net (code "85") (name "unconnected-(XTAL1-TRI-Pad1)") (class "Default")
      (node (ref "XTAL1") (pin "1") (pinfunction "TRI_1") (pintype "bidirectional"))
    )
  )
)
